# LevelSensor.net
KiCad netlist of a schematic drawn in EAGLE
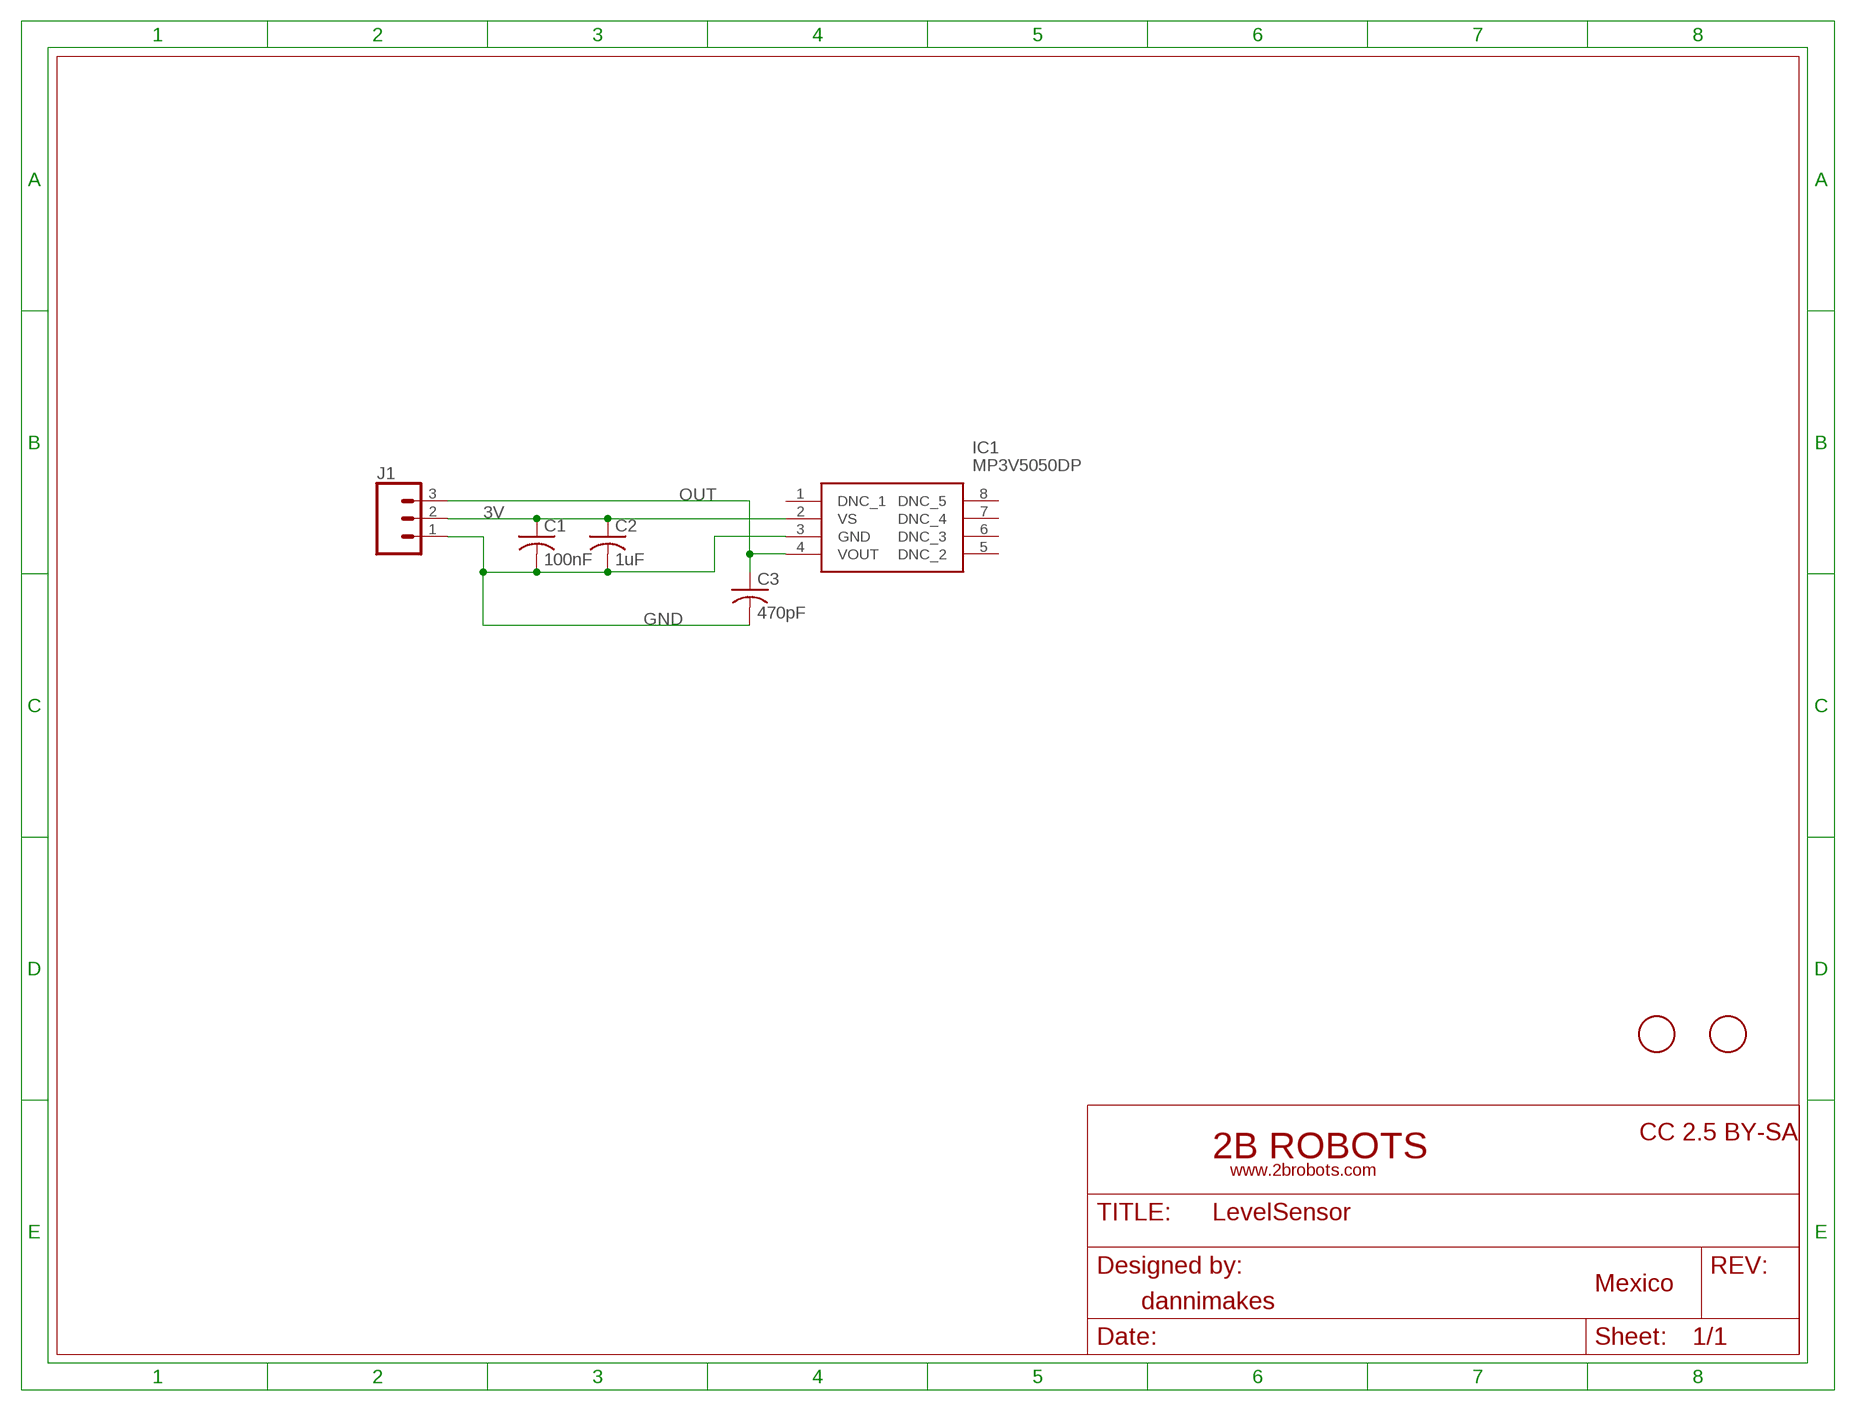
[diagram p0: schematic, sheet 1]

(export (version "E")
  (design (tool "Eeschema 10.0.6"))
  (components
    (comp (ref "C1")
      (value "100nF")
      (footprint "eagle-import:C0603K")
      (libsource (lib "eagle-import") (part "C-USC0603K"))
    )
    (comp (ref "C2")
      (value "1uF")
      (footprint "eagle-import:C0603K")
      (libsource (lib "eagle-import") (part "C-USC0603K"))
    )
    (comp (ref "C3")
      (value "470pF")
      (footprint "eagle-import:C0805K")
      (libsource (lib "eagle-import") (part "C-USC0805K"))
    )
    (comp (ref "IC1")
      (value "MP3V5050DP")
      (footprint "eagle-import:SOP254P1753X991-8N")
      (fields (field (name "MOUSER_PART_NUMBER") "841-MP3V5050DP"))
      (libsource (lib "eagle-import") (part "MP3V5050DP"))
    )
    (comp (ref "J1")
      (value "CONN_03-SCREW-5MM")
      (footprint "eagle-import:SCREWTERMINAL-5MM-3")
      (libsource (lib "eagle-import") (part "CONN_03-SCREW-5MM"))
    )
    (comp (ref "U$2")
      (value "FIDUCIAL")
      (footprint "eagle-import:FIDUCIAL_1MM")
      (libsource (lib "eagle-import") (part "FIDUCIAL"))
    )
    (comp (ref "U$3")
      (value "FIDUCIAL")
      (footprint "eagle-import:FIDUCIAL_1MM")
      (libsource (lib "eagle-import") (part "FIDUCIAL"))
    )
  )
  (nets
    (net (code "1") (name "/3V") (class "Default")
      (node (ref "C1") (pin "1") (pinfunction "1_1") (pintype "passive"))
      (node (ref "C2") (pin "1") (pinfunction "1_1") (pintype "passive"))
      (node (ref "IC1") (pin "2") (pinfunction "VS_2") (pintype "bidirectional"))
      (node (ref "J1") (pin "2") (pinfunction "2_2") (pintype "passive"))
    )
    (net (code "2") (name "/GND") (class "Default")
      (node (ref "C1") (pin "2") (pinfunction "2_2") (pintype "passive"))
      (node (ref "C2") (pin "2") (pinfunction "2_2") (pintype "passive"))
      (node (ref "C3") (pin "2") (pinfunction "2_2") (pintype "passive"))
      (node (ref "IC1") (pin "3") (pinfunction "GND_3") (pintype "bidirectional"))
      (node (ref "J1") (pin "1") (pinfunction "1_1") (pintype "passive"))
    )
    (net (code "3") (name "/OUT") (class "Default")
      (node (ref "C3") (pin "1") (pinfunction "1_1") (pintype "passive"))
      (node (ref "IC1") (pin "4") (pinfunction "VOUT_4") (pintype "bidirectional"))
      (node (ref "J1") (pin "3") (pinfunction "3_3") (pintype "passive"))
    )
    (net (code "4") (name "unconnected-(IC1-DNC_1-Pad1)") (class "Default")
      (node (ref "IC1") (pin "1") (pinfunction "DNC_1_1") (pintype "bidirectional"))
    )
    (net (code "5") (name "unconnected-(IC1-DNC_2-Pad5)") (class "Default")
      (node (ref "IC1") (pin "5") (pinfunction "DNC_2_5") (pintype "bidirectional"))
    )
    (net (code "6") (name "unconnected-(IC1-DNC_3-Pad6)") (class "Default")
      (node (ref "IC1") (pin "6") (pinfunction "DNC_3_6") (pintype "bidirectional"))
    )
    (net (code "7") (name "unconnected-(IC1-DNC_4-Pad7)") (class "Default")
      (node (ref "IC1") (pin "7") (pinfunction "DNC_4_7") (pintype "bidirectional"))
    )
    (net (code "8") (name "unconnected-(IC1-DNC_5-Pad8)") (class "Default")
      (node (ref "IC1") (pin "8") (pinfunction "DNC_5_8") (pintype "bidirectional"))
    )
  )
)
